# CH32F207VCT6-R0.net
KiCad netlist of a schematic drawn in Altium Designer
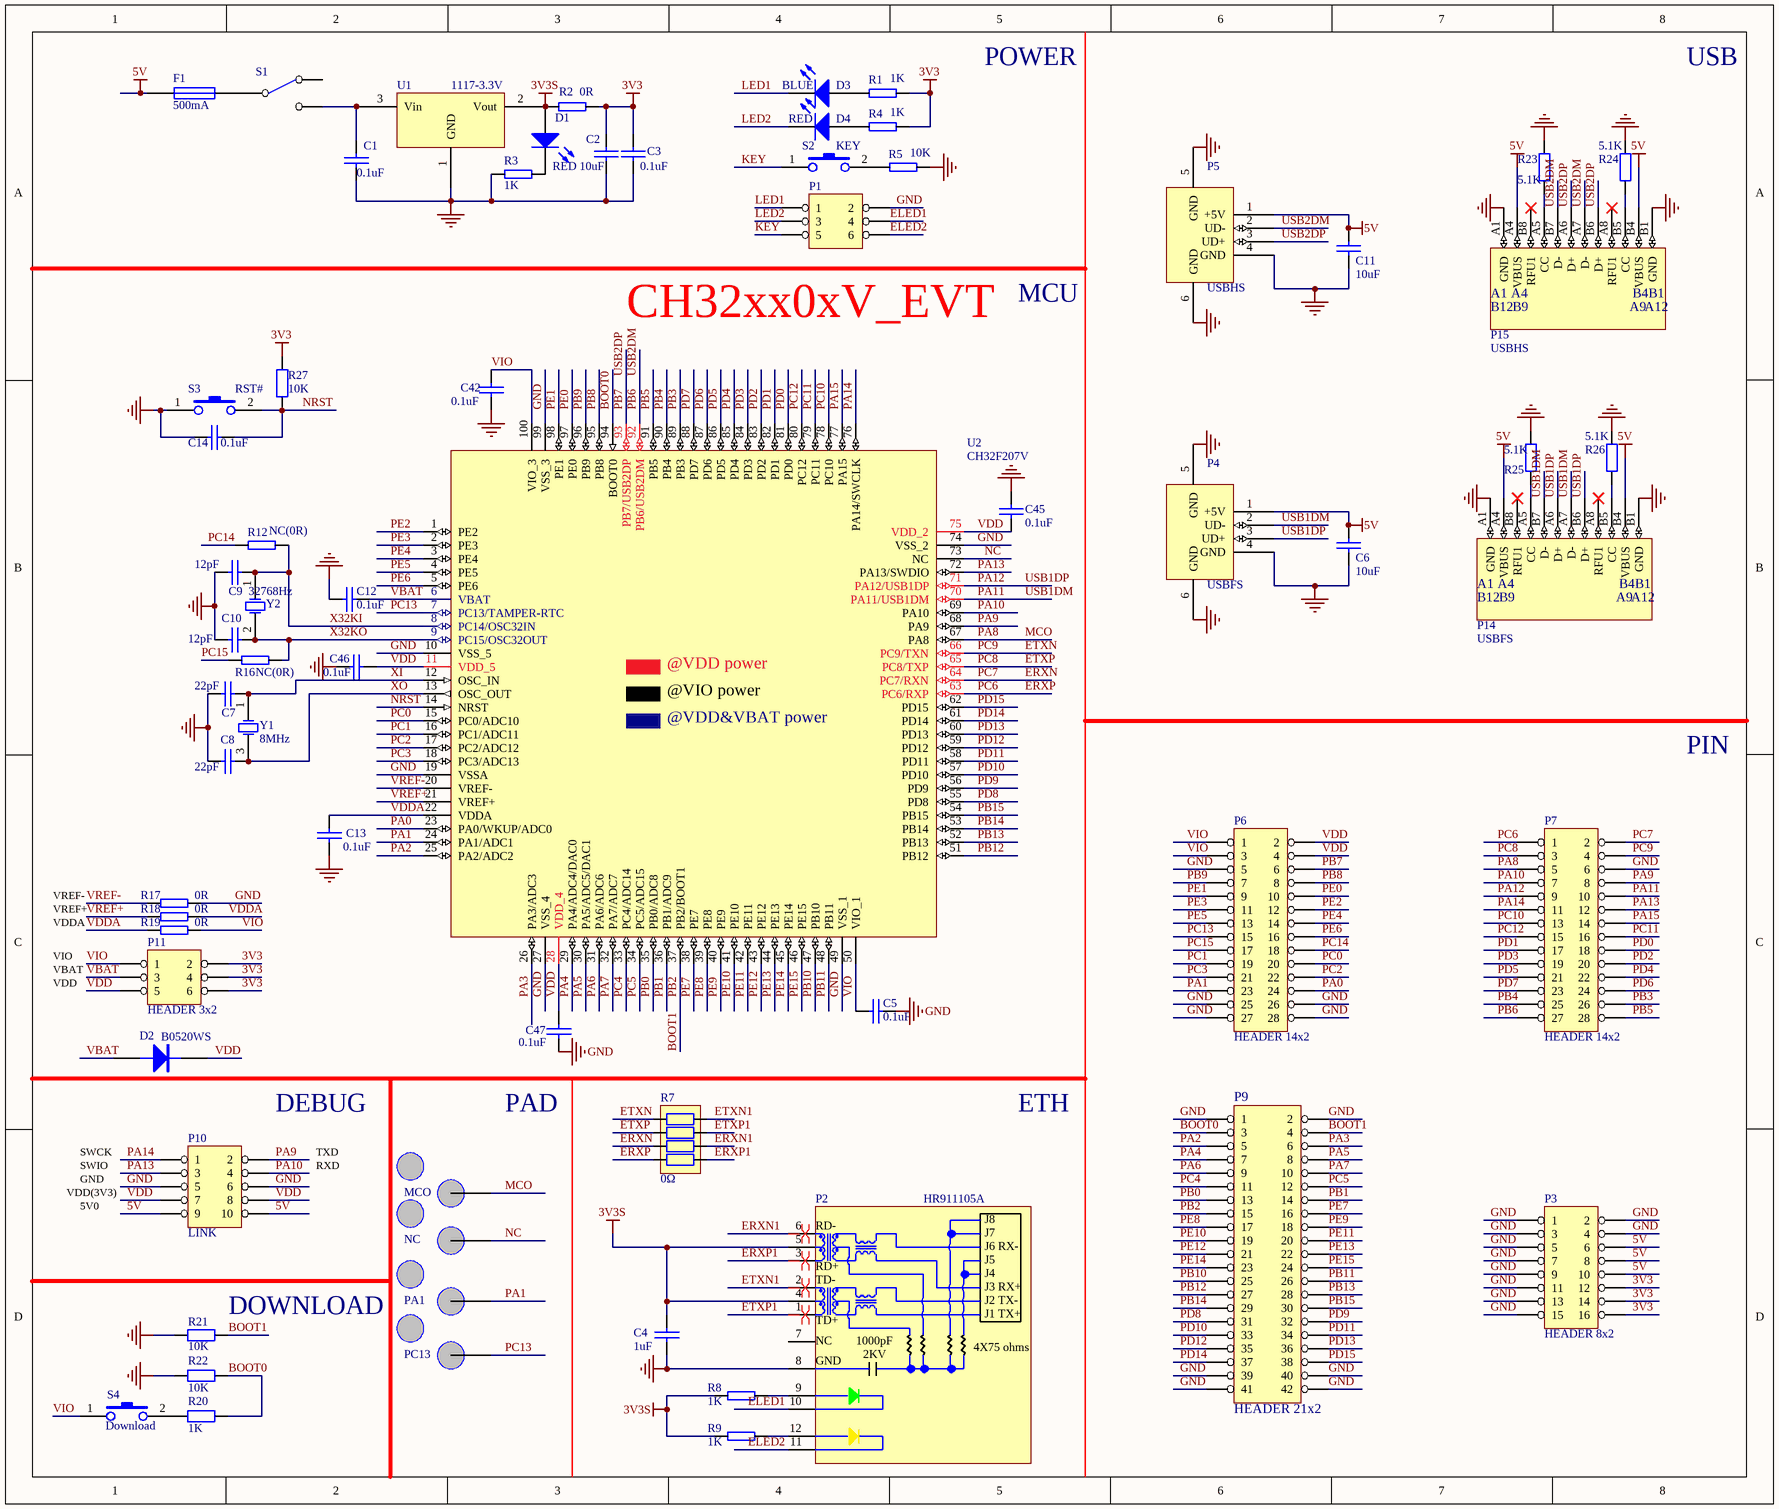
[diagram p0: CH32F207VCT6-R0.SchDoc]

(export (version "E")
  (design (tool "Eeschema 10.0.6"))
  (components
    (comp (ref "C1")
      (value "0.1uF")
      (footprint "0603_C")
      (description "Capacitor")
      (libsource (lib "") (part "CAP_1"))
    )
    (comp (ref "C2")
      (value "10uF")
      (footprint "3216_C")
      (description "Capacitor")
      (libsource (lib "") (part "CAP_1"))
    )
    (comp (ref "C3")
      (value "0.1uF")
      (footprint "0603_C")
      (description "Capacitor")
      (libsource (lib "") (part "CAP_1"))
    )
    (comp (ref "C4")
      (value "1uF")
      (footprint "0603_C")
      (description "Capacitor")
      (libsource (lib "") (part "CAP_1"))
    )
    (comp (ref "C5")
      (value "0.1uF")
      (footprint "0603_C")
      (description "Capacitor")
      (libsource (lib "") (part "CAP_1"))
    )
    (comp (ref "C6")
      (value "10uF")
      (footprint "3216_C")
      (description "Capacitor")
      (libsource (lib "*") (part "CAP"))
    )
    (comp (ref "C7")
      (value "22pF")
      (footprint "0603_C")
      (description "Capacitor")
      (libsource (lib "") (part "CAP_1"))
    )
    (comp (ref "C8")
      (value "22pF")
      (footprint "0603_C")
      (description "Capacitor")
      (libsource (lib "") (part "CAP_1"))
    )
    (comp (ref "C9")
      (value "12pF")
      (footprint "0603_C")
      (description "Capacitor")
      (libsource (lib "") (part "CAP_1"))
    )
    (comp (ref "C10")
      (value "12pF")
      (footprint "0603_C")
      (description "Capacitor")
      (libsource (lib "") (part "CAP_1"))
    )
    (comp (ref "C11")
      (value "10uF")
      (footprint "3216_C")
      (description "Capacitor")
      (libsource (lib "*") (part "CAP"))
    )
    (comp (ref "C12")
      (value "0.1uF")
      (footprint "0603_C")
      (description "Capacitor")
      (libsource (lib "") (part "CAP_1"))
    )
    (comp (ref "C13")
      (value "0.1uF")
      (footprint "0603_C")
      (description "Capacitor")
      (libsource (lib "") (part "CAP_1"))
    )
    (comp (ref "C14")
      (value "0.1uF")
      (footprint "0603_C")
      (description "Capacitor")
      (libsource (lib "*") (part "CAP"))
    )
    (comp (ref "C42")
      (value "0.1uF")
      (footprint "0603_C")
      (description "Capacitor")
      (libsource (lib "") (part "CAP_1"))
    )
    (comp (ref "C45")
      (value "0.1uF")
      (footprint "0603_C")
      (description "Capacitor")
      (libsource (lib "") (part "CAP_1"))
    )
    (comp (ref "C46")
      (value "0.1uF")
      (footprint "0603_C")
      (description "Capacitor")
      (libsource (lib "") (part "CAP_1"))
    )
    (comp (ref "C47")
      (value "0.1uF")
      (footprint "0603_C")
      (description "Capacitor")
      (libsource (lib "") (part "CAP_1"))
    )
    (comp (ref "D1")
      (value "RED")
      (footprint "0603+")
      (description "Typical INFRARED GaAs LED")
      (fields (field (name "PUBLISHER") "Altium Limited"))
      (libsource (lib "*") (part "LED0"))
    )
    (comp (ref "D2")
      (value "B0520WS")
      (footprint "SOD-323")
      (description "Diode")
      (libsource (lib "*") (part "DIODE"))
    )
    (comp (ref "D3")
      (value "BLUE")
      (footprint "0603+")
      (description "Typical INFRARED GaAs LED")
      (fields (field (name "PUBLISHER") "Altium Limited"))
      (libsource (lib "*") (part "LED0"))
    )
    (comp (ref "D4")
      (value "RED")
      (footprint "0603+")
      (description "Typical INFRARED GaAs LED")
      (fields (field (name "PUBLISHER") "Altium Limited"))
      (libsource (lib "*") (part "LED0"))
    )
    (comp (ref "F1")
      (value "500mA")
      (footprint "0805")
      (description "Fuse")
      (libsource (lib "wch_sch_others") (part "FUSE1"))
    )
    (comp (ref "MCO")
      (value "Testpoint")
      (footprint "TESTPOINT1")
      (description "测试点")
      (libsource (lib "wch_sch_others") (part "Testpoint"))
    )
    (comp (ref "NC")
      (value "Testpoint")
      (footprint "TESTPOINT1")
      (description "测试点")
      (libsource (lib "wch_sch_others") (part "Testpoint"))
    )
    (comp (ref "P1")
      (value "IO")
      (footprint "MYPCB:IDC6-2.54mm")
      (description "Header, 3-Pin, Dual row")
      (libsource (lib "wch_sch_others") (part "HEADER 3x2"))
    )
    (comp (ref "P2") (value "HR911105A") (footprint "HR911105A") (libsource (lib "*") (part "HR911105A")))
    (comp (ref "P3")
      (value "HEADER 8x2")
      (footprint "MYPCB:IDC16-2.54mm")
      (description "Header, 8-Pin, Dual row")
      (libsource (lib "wch_sch_others") (part "HEADER 8x2"))
    )
    (comp (ref "P4")
      (value "USBFS")
      (footprint "USBAF")
      (description "USB Port")
      (libsource (lib "*") (part "USB"))
    )
    (comp (ref "P5")
      (value "USBHS")
      (footprint "USBAF")
      (description "USB Port")
      (libsource (lib "*") (part "USB"))
    )
    (comp (ref "P6")
      (value "HEADER 14x2")
      (footprint "MYPCB:IDC28-2.54MM")
      (description "Header, 14-Pin, Dual row")
      (libsource (lib "wch_sch_others") (part "HEADER 14x2"))
    )
    (comp (ref "P7")
      (value "HEADER 14x2")
      (footprint "MYPCB:IDC28-2.54MM")
      (description "Header, 14-Pin, Dual row")
      (libsource (lib "wch_sch_others") (part "HEADER 14x2"))
    )
    (comp (ref "P9")
      (value "HEADER 21x2")
      (footprint "MYPCB:IDC42-2.54MM")
      (description "Header, 21-Pin, Dual row")
      (libsource (lib "wch_sch_others") (part "HEADER 21x2"))
    )
    (comp (ref "P10")
      (value "LINK")
      (footprint "MYPCB:IDC10-2.54mm")
      (description "Header, 5-Pin, Dual row")
      (libsource (lib "wch_sch_others") (part "HEADER 5x2"))
    )
    (comp (ref "P11")
      (value "HEADER 3x2")
      (footprint "MYPCB:IDC6-2.54mm")
      (description "Header, 3-Pin, Dual row")
      (libsource (lib "wch_sch_others") (part "HEADER 3x2"))
    )
    (comp (ref "P14")
      (value "USBFS")
      (footprint "TYPE-C-Receptacle-2.0")
      (libsource (lib "*") (part "TYPE-C1"))
    )
    (comp (ref "P15")
      (value "USBHS")
      (footprint "TYPE-C-Receptacle-2.0")
      (libsource (lib "*") (part "TYPE-C1"))
    )
    (comp (ref "PA1")
      (value "Testpoint")
      (footprint "TESTPOINT1")
      (description "测试点")
      (libsource (lib "wch_sch_others") (part "Testpoint"))
    )
    (comp (ref "PC13")
      (value "Testpoint")
      (footprint "TESTPOINT1")
      (description "测试点")
      (libsource (lib "wch_sch_others") (part "Testpoint"))
    )
    (comp (ref "R1") (value "1K") (footprint "0603") (libsource (lib "wch_sch_others") (part "RES")))
    (comp (ref "R2") (value "0R") (footprint "0603") (libsource (lib "wch_sch_others") (part "RES")))
    (comp (ref "R3") (value "1K") (footprint "0603") (libsource (lib "wch_sch_others") (part "RES")))
    (comp (ref "R4") (value "1K") (footprint "0603") (libsource (lib "wch_sch_others") (part "RES")))
    (comp (ref "R5") (value "10K") (footprint "0603") (libsource (lib "wch_sch_others") (part "RES")))
    (comp (ref "R7")
      (value "0Ω")
      (footprint "RCA-8P4R-0603")
      (description "贴片网络排阻")
      (fields (field (name "版权归属") "源创客"))
      (libsource (lib "wch_sch_others") (part "R-8P4R"))
    )
    (comp (ref "R8") (value "1K") (footprint "0603") (libsource (lib "wch_sch_others") (part "RES")))
    (comp (ref "R9") (value "1K") (footprint "0603") (libsource (lib "wch_sch_others") (part "RES")))
    (comp (ref "R12") (value "NC(0R)") (footprint "0603") (libsource (lib "wch_sch_others") (part "RES")))
    (comp (ref "R16") (value "NC(0R)") (footprint "0603") (libsource (lib "wch_sch_others") (part "RES")))
    (comp (ref "R17") (value "0R") (footprint "0603") (libsource (lib "*") (part "R")))
    (comp (ref "R18") (value "0R") (footprint "0603") (libsource (lib "*") (part "R")))
    (comp (ref "R19") (value "0R") (footprint "0603") (libsource (lib "*") (part "R")))
    (comp (ref "R20")
      (value "1K")
      (footprint "0603")
      (description "Resistor")
      (fields (field (name "PUBLISHER") "Altium Limited"))
      (libsource (lib "Miscellaneous Devices") (part "Res2"))
    )
    (comp (ref "R21")
      (value "10K")
      (footprint "0603")
      (description "Resistor")
      (fields (field (name "PUBLISHER") "Altium Limited"))
      (libsource (lib "Miscellaneous Devices") (part "Res2"))
    )
    (comp (ref "R22")
      (value "10K")
      (footprint "0603")
      (description "Resistor")
      (fields (field (name "PUBLISHER") "Altium Limited"))
      (libsource (lib "Miscellaneous Devices") (part "Res2"))
    )
    (comp (ref "R23")
      (value "5.1K")
      (footprint "0603")
      (description "Resistor")
      (libsource (lib "") (part "Res2_1"))
    )
    (comp (ref "R24")
      (value "5.1K")
      (footprint "0603")
      (description "Resistor")
      (libsource (lib "") (part "Res2_1"))
    )
    (comp (ref "R25")
      (value "5.1K")
      (footprint "0603")
      (description "Resistor")
      (libsource (lib "") (part "Res2_1"))
    )
    (comp (ref "R26")
      (value "5.1K")
      (footprint "0603")
      (description "Resistor")
      (libsource (lib "") (part "Res2_1"))
    )
    (comp (ref "R27")
      (value "10K")
      (footprint "0603")
      (description "Resistor")
      (fields (field (name "PUBLISHER") "Altium Limited"))
      (libsource (lib "") (part "Res2_1"))
    )
    (comp (ref "S1") (value "SW SPDT") (footprint "KEY2") (libsource (lib "*") (part "SW SPDT")))
    (comp (ref "S2")
      (value "KEY")
      (footprint "SMD_6.1x3.65x2.5mm-KEY")
      (libsource (lib "wch_sch_others") (part "KEY1"))
    )
    (comp (ref "S3")
      (value "RST#")
      (footprint "SMD_6.1x3.65x2.5mm-KEY")
      (libsource (lib "wch_sch_others") (part "KEY1"))
    )
    (comp (ref "S4")
      (value "Download")
      (footprint "SMD_6.1x3.65x2.5mm-KEY")
      (libsource (lib "wch_sch_others") (part "KEY1"))
    )
    (comp (ref "U1")
      (value "1117-3.3V")
      (footprint "SOT-223")
      (libsource (lib "wch_sch_others") (part "1117-3.3V"))
    )
    (comp (ref "U2")
      (value "CH32F207V")
      (footprint "LQFP100")
      (description "ARM M3 HD-MCU, 144MHz, USB_480M, USB OTG, 1000M Ethernet MAC, 2*CAN")
      (libsource (lib "CHXXX") (part "CH32F207V"))
    )
    (comp (ref "Y1")
      (value "8MHz")
      (footprint "XT3225")
      (description "Crystal Oscillator")
      (fields (field (name "PUBLISHER") "Altium Limited"))
      (libsource (lib "*") (part "XTAL"))
    )
    (comp (ref "Y2")
      (value "32768Hz")
      (footprint "FC-135")
      (description "Crystal Oscillator")
      (fields (field (name "PUBLISHER") "Altium Limited"))
      (libsource (lib "") (part "XTAL_1"))
    )
  )
  (nets
    (net (code "2") (name "/BOOT0") (class "Default")
      (node (ref "P9") (pin "3") (pinfunction "3_3") (pintype "passive"))
      (node (ref "R20") (pin "1") (pinfunction "1_1") (pintype "passive"))
      (node (ref "R22") (pin "1") (pinfunction "1_1") (pintype "passive"))
      (node (ref "U2") (pin "94") (pinfunction "BOOT0_94") (pintype "input"))
    )
    (net (code "3") (name "/BOOT1") (class "Default")
      (node (ref "P9") (pin "15") (pinfunction "15_15") (pintype "passive"))
      (node (ref "P9") (pin "4") (pinfunction "4_4") (pintype "passive"))
      (node (ref "R21") (pin "1") (pinfunction "1_1") (pintype "passive"))
      (node (ref "U2") (pin "37") (pinfunction "PB2/BOOT1_37") (pintype "bidirectional"))
    )
    (net (code "4") (name "/ELED1") (class "Default")
      (node (ref "P1") (pin "4") (pinfunction "4_4") (pintype "passive"))
      (node (ref "P2") (pin "10") (pintype "passive"))
    )
    (net (code "5") (name "/ELED2") (class "Default")
      (node (ref "P1") (pin "6") (pinfunction "6_6") (pintype "passive"))
      (node (ref "P2") (pin "11") (pintype "passive"))
    )
    (net (code "6") (name "/ERXN") (class "Default")
      (node (ref "P7") (pin "2") (pinfunction "2_2") (pintype "passive"))
      (node (ref "R7") (pin "3") (pinfunction "3_3") (pintype "passive"))
      (node (ref "U2") (pin "64") (pinfunction "PC7/RXN_64") (pintype "bidirectional"))
    )
    (net (code "7") (name "/ERXN1") (class "Default")
      (node (ref "P2") (pin "6") (pintype "passive"))
      (node (ref "R7") (pin "6") (pinfunction "6_6") (pintype "passive"))
    )
    (net (code "8") (name "/ERXP") (class "Default")
      (node (ref "P7") (pin "1") (pinfunction "1_1") (pintype "passive"))
      (node (ref "R7") (pin "4") (pinfunction "4_4") (pintype "passive"))
      (node (ref "U2") (pin "63") (pinfunction "PC6/RXP_63") (pintype "bidirectional"))
    )
    (net (code "9") (name "/ERXP1") (class "Default")
      (node (ref "P2") (pin "3") (pintype "passive"))
      (node (ref "R7") (pin "5") (pinfunction "5_5") (pintype "passive"))
    )
    (net (code "10") (name "/ETXN") (class "Default")
      (node (ref "P7") (pin "4") (pinfunction "4_4") (pintype "passive"))
      (node (ref "R7") (pin "1") (pinfunction "1_1") (pintype "passive"))
      (node (ref "U2") (pin "66") (pinfunction "PC9/TXN_66") (pintype "bidirectional"))
    )
    (net (code "11") (name "/ETXN1") (class "Default")
      (node (ref "P2") (pin "2") (pintype "passive"))
      (node (ref "R7") (pin "8") (pinfunction "8_8") (pintype "passive"))
    )
    (net (code "12") (name "/ETXP") (class "Default")
      (node (ref "P7") (pin "3") (pinfunction "3_3") (pintype "passive"))
      (node (ref "R7") (pin "2") (pinfunction "2_2") (pintype "passive"))
      (node (ref "U2") (pin "65") (pinfunction "PC8/TXP_65") (pintype "bidirectional"))
    )
    (net (code "13") (name "/ETXP1") (class "Default")
      (node (ref "P2") (pin "1") (pintype "passive"))
      (node (ref "R7") (pin "7") (pinfunction "7_7") (pintype "passive"))
    )
    (net (code "14") (name "/KEY") (class "Default")
      (node (ref "P1") (pin "5") (pinfunction "5_5") (pintype "passive"))
      (node (ref "S2") (pin "1") (pinfunction "1_1") (pintype "passive"))
    )
    (net (code "15") (name "/LED1") (class "Default")
      (node (ref "D3") (pin "2") (pinfunction "K_2") (pintype "passive"))
      (node (ref "P1") (pin "1") (pinfunction "1_1") (pintype "passive"))
    )
    (net (code "16") (name "/LED2") (class "Default")
      (node (ref "D4") (pin "2") (pinfunction "K_2") (pintype "passive"))
      (node (ref "P1") (pin "3") (pinfunction "3_3") (pintype "passive"))
    )
    (net (code "17") (name "/MCO") (class "Default")
      (node (ref "MCO") (pin "1") (pinfunction "point_1") (pintype "passive"))
      (node (ref "P7") (pin "5") (pinfunction "5_5") (pintype "passive"))
      (node (ref "U2") (pin "67") (pinfunction "PA8_67") (pintype "bidirectional"))
    )
    (net (code "18") (name "/NC") (class "Default")
      (node (ref "NC") (pin "1") (pinfunction "point_1") (pintype "passive"))
      (node (ref "U2") (pin "73") (pinfunction "NC_73") (pintype "tri_state"))
    )
    (net (code "19") (name "/NRST") (class "Default")
      (node (ref "C14") (pin "2") (pinfunction "2_2") (pintype "passive"))
      (node (ref "R27") (pin "1") (pinfunction "1_1") (pintype "passive"))
      (node (ref "S3") (pin "2") (pinfunction "2_2") (pintype "passive"))
      (node (ref "U2") (pin "14") (pinfunction "NRST_14") (pintype "input"))
    )
    (net (code "20") (name "/PA0") (class "Default")
      (node (ref "P6") (pin "24") (pinfunction "24_24") (pintype "passive"))
      (node (ref "U2") (pin "23") (pinfunction "PA0/WKUP/ADC0_23") (pintype "bidirectional"))
    )
    (net (code "21") (name "/PA1") (class "Default")
      (node (ref "P6") (pin "23") (pinfunction "23_23") (pintype "passive"))
      (node (ref "PA1") (pin "1") (pinfunction "point_1") (pintype "passive"))
      (node (ref "U2") (pin "24") (pinfunction "PA1/ADC1_24") (pintype "bidirectional"))
    )
    (net (code "22") (name "/PA2") (class "Default")
      (node (ref "P9") (pin "5") (pinfunction "5_5") (pintype "passive"))
      (node (ref "U2") (pin "25") (pinfunction "PA2/ADC2_25") (pintype "bidirectional"))
    )
    (net (code "23") (name "/PA3") (class "Default")
      (node (ref "P9") (pin "6") (pinfunction "6_6") (pintype "passive"))
      (node (ref "U2") (pin "26") (pinfunction "PA3/ADC3_26") (pintype "bidirectional"))
    )
    (net (code "24") (name "/PA4") (class "Default")
      (node (ref "P9") (pin "7") (pinfunction "7_7") (pintype "passive"))
      (node (ref "U2") (pin "29") (pinfunction "PA4/ADC4/DAC0_29") (pintype "bidirectional"))
    )
    (net (code "25") (name "/PA5") (class "Default")
      (node (ref "P9") (pin "8") (pinfunction "8_8") (pintype "passive"))
      (node (ref "U2") (pin "30") (pinfunction "PA5/ADC5/DAC1_30") (pintype "bidirectional"))
    )
    (net (code "26") (name "/PA6") (class "Default")
      (node (ref "P9") (pin "9") (pinfunction "9_9") (pintype "passive"))
      (node (ref "U2") (pin "31") (pinfunction "PA6/ADC6_31") (pintype "bidirectional"))
    )
    (net (code "27") (name "/PA7") (class "Default")
      (node (ref "P9") (pin "10") (pinfunction "10_10") (pintype "passive"))
      (node (ref "U2") (pin "32") (pinfunction "PA7/ADC7_32") (pintype "bidirectional"))
    )
    (net (code "28") (name "/PA9") (class "Default")
      (node (ref "P10") (pin "2") (pinfunction "2_2") (pintype "passive"))
      (node (ref "P7") (pin "8") (pinfunction "8_8") (pintype "passive"))
      (node (ref "U2") (pin "68") (pinfunction "PA9_68") (pintype "bidirectional"))
    )
    (net (code "29") (name "/PA10") (class "Default")
      (node (ref "P10") (pin "4") (pinfunction "4_4") (pintype "passive"))
      (node (ref "P7") (pin "7") (pinfunction "7_7") (pintype "passive"))
      (node (ref "U2") (pin "69") (pinfunction "PA10_69") (pintype "bidirectional"))
    )
    (net (code "30") (name "/PA11") (class "Default")
      (node (ref "P14") (pin "A7") (pinfunction "D-_A7") (pintype "bidirectional"))
      (node (ref "P14") (pin "B7") (pinfunction "D-_B7") (pintype "bidirectional"))
      (node (ref "P4") (pin "2") (pinfunction "UD-_2") (pintype "bidirectional"))
      (node (ref "P7") (pin "10") (pinfunction "10_10") (pintype "passive"))
      (node (ref "U2") (pin "70") (pinfunction "PA11/USB1DM_70") (pintype "bidirectional"))
    )
    (net (code "31") (name "/PA12") (class "Default")
      (node (ref "P14") (pin "A6") (pinfunction "D+_A6") (pintype "bidirectional"))
      (node (ref "P14") (pin "B6") (pinfunction "D+_B6") (pintype "bidirectional"))
      (node (ref "P4") (pin "3") (pinfunction "UD+_3") (pintype "bidirectional"))
      (node (ref "P7") (pin "9") (pinfunction "9_9") (pintype "passive"))
      (node (ref "U2") (pin "71") (pinfunction "PA12/USB1DP_71") (pintype "bidirectional"))
    )
    (net (code "32") (name "/PA13") (class "Default")
      (node (ref "P10") (pin "3") (pinfunction "3_3") (pintype "passive"))
      (node (ref "P7") (pin "12") (pinfunction "12_12") (pintype "passive"))
      (node (ref "U2") (pin "72") (pinfunction "PA13/SWDIO_72") (pintype "bidirectional"))
    )
    (net (code "33") (name "/PA14") (class "Default")
      (node (ref "P10") (pin "1") (pinfunction "1_1") (pintype "passive"))
      (node (ref "P7") (pin "11") (pinfunction "11_11") (pintype "passive"))
      (node (ref "U2") (pin "76") (pinfunction "PA14/SWCLK_76") (pintype "bidirectional"))
    )
    (net (code "34") (name "/PA15") (class "Default")
      (node (ref "P7") (pin "14") (pinfunction "14_14") (pintype "passive"))
      (node (ref "U2") (pin "77") (pinfunction "PA15_77") (pintype "bidirectional"))
    )
    (net (code "35") (name "/PB0") (class "Default")
      (node (ref "P9") (pin "13") (pinfunction "13_13") (pintype "passive"))
      (node (ref "U2") (pin "35") (pinfunction "PB0/ADC8_35") (pintype "bidirectional"))
    )
    (net (code "36") (name "/PB1") (class "Default")
      (node (ref "P9") (pin "14") (pinfunction "14_14") (pintype "passive"))
      (node (ref "U2") (pin "36") (pinfunction "PB1/ADC9_36") (pintype "bidirectional"))
    )
    (net (code "37") (name "/PB3") (class "Default")
      (node (ref "P7") (pin "26") (pinfunction "26_26") (pintype "passive"))
      (node (ref "U2") (pin "89") (pinfunction "PB3_89") (pintype "bidirectional"))
    )
    (net (code "38") (name "/PB4") (class "Default")
      (node (ref "P7") (pin "25") (pinfunction "25_25") (pintype "passive"))
      (node (ref "U2") (pin "90") (pinfunction "PB4_90") (pintype "bidirectional"))
    )
    (net (code "39") (name "/PB5") (class "Default")
      (node (ref "P7") (pin "28") (pinfunction "28_28") (pintype "passive"))
      (node (ref "U2") (pin "91") (pinfunction "PB5_91") (pintype "bidirectional"))
    )
    (net (code "40") (name "/PB6") (class "Default")
      (node (ref "P15") (pin "A7") (pinfunction "D-_A7") (pintype "bidirectional"))
      (node (ref "P15") (pin "B7") (pinfunction "D-_B7") (pintype "bidirectional"))
      (node (ref "P5") (pin "2") (pinfunction "UD-_2") (pintype "bidirectional"))
      (node (ref "P7") (pin "27") (pinfunction "27_27") (pintype "passive"))
      (node (ref "U2") (pin "92") (pinfunction "PB6/USB2DM_92") (pintype "bidirectional"))
    )
    (net (code "41") (name "/PB7") (class "Default")
      (node (ref "P15") (pin "A6") (pinfunction "D+_A6") (pintype "bidirectional"))
      (node (ref "P15") (pin "B6") (pinfunction "D+_B6") (pintype "bidirectional"))
      (node (ref "P5") (pin "3") (pinfunction "UD+_3") (pintype "bidirectional"))
      (node (ref "P6") (pin "6") (pinfunction "6_6") (pintype "passive"))
      (node (ref "U2") (pin "93") (pinfunction "PB7/USB2DP_93") (pintype "bidirectional"))
    )
    (net (code "42") (name "/PB8") (class "Default")
      (node (ref "P6") (pin "8") (pinfunction "8_8") (pintype "passive"))
      (node (ref "U2") (pin "95") (pinfunction "PB8_95") (pintype "bidirectional"))
    )
    (net (code "43") (name "/PB9") (class "Default")
      (node (ref "P6") (pin "7") (pinfunction "7_7") (pintype "passive"))
      (node (ref "U2") (pin "96") (pinfunction "PB9_96") (pintype "bidirectional"))
    )
    (net (code "44") (name "/PB10") (class "Default")
      (node (ref "P9") (pin "25") (pinfunction "25_25") (pintype "passive"))
      (node (ref "U2") (pin "47") (pinfunction "PB10_47") (pintype "bidirectional"))
    )
    (net (code "45") (name "/PB11") (class "Default")
      (node (ref "P9") (pin "26") (pinfunction "26_26") (pintype "passive"))
      (node (ref "U2") (pin "48") (pinfunction "PB11_48") (pintype "bidirectional"))
    )
    (net (code "46") (name "/PB12") (class "Default")
      (node (ref "P9") (pin "27") (pinfunction "27_27") (pintype "passive"))
      (node (ref "U2") (pin "51") (pinfunction "PB12_51") (pintype "bidirectional"))
    )
    (net (code "47") (name "/PB13") (class "Default")
      (node (ref "P9") (pin "28") (pinfunction "28_28") (pintype "passive"))
      (node (ref "U2") (pin "52") (pinfunction "PB13_52") (pintype "bidirectional"))
    )
    (net (code "48") (name "/PB14") (class "Default")
      (node (ref "P9") (pin "29") (pinfunction "29_29") (pintype "passive"))
      (node (ref "U2") (pin "53") (pinfunction "PB14_53") (pintype "bidirectional"))
    )
    (net (code "49") (name "/PB15") (class "Default")
      (node (ref "P9") (pin "30") (pinfunction "30_30") (pintype "passive"))
      (node (ref "U2") (pin "54") (pinfunction "PB15_54") (pintype "bidirectional"))
    )
    (net (code "50") (name "/PC0") (class "Default")
      (node (ref "P6") (pin "20") (pinfunction "20_20") (pintype "passive"))
      (node (ref "U2") (pin "15") (pinfunction "PC0/ADC10_15") (pintype "bidirectional"))
    )
    (net (code "51") (name "/PC1") (class "Default")
      (node (ref "P6") (pin "19") (pinfunction "19_19") (pintype "passive"))
      (node (ref "U2") (pin "16") (pinfunction "PC1/ADC11_16") (pintype "bidirectional"))
    )
    (net (code "52") (name "/PC2") (class "Default")
      (node (ref "P6") (pin "22") (pinfunction "22_22") (pintype "passive"))
      (node (ref "U2") (pin "17") (pinfunction "PC2/ADC12_17") (pintype "bidirectional"))
    )
    (net (code "53") (name "/PC3") (class "Default")
      (node (ref "P6") (pin "21") (pinfunction "21_21") (pintype "passive"))
      (node (ref "U2") (pin "18") (pinfunction "PC3/ADC13_18") (pintype "bidirectional"))
    )
    (net (code "54") (name "/PC4") (class "Default")
      (node (ref "P9") (pin "11") (pinfunction "11_11") (pintype "passive"))
      (node (ref "U2") (pin "33") (pinfunction "PC4/ADC14_33") (pintype "bidirectional"))
    )
    (net (code "55") (name "/PC5") (class "Default")
      (node (ref "P9") (pin "12") (pinfunction "12_12") (pintype "passive"))
      (node (ref "U2") (pin "34") (pinfunction "PC5/ADC15_34") (pintype "bidirectional"))
    )
    (net (code "56") (name "/PC10") (class "Default")
      (node (ref "P7") (pin "13") (pinfunction "13_13") (pintype "passive"))
      (node (ref "U2") (pin "78") (pinfunction "PC10_78") (pintype "bidirectional"))
    )
    (net (code "57") (name "/PC11") (class "Default")
      (node (ref "P7") (pin "16") (pinfunction "16_16") (pintype "passive"))
      (node (ref "U2") (pin "79") (pinfunction "PC11_79") (pintype "bidirectional"))
    )
    (net (code "58") (name "/PC12") (class "Default")
      (node (ref "P7") (pin "15") (pinfunction "15_15") (pintype "passive"))
      (node (ref "U2") (pin "80") (pinfunction "PC12_80") (pintype "bidirectional"))
    )
    (net (code "59") (name "/PC13") (class "Default")
      (node (ref "P6") (pin "15") (pinfunction "15_15") (pintype "passive"))
      (node (ref "PC13") (pin "1") (pinfunction "point_1") (pintype "passive"))
      (node (ref "U2") (pin "7") (pinfunction "PC13/TAMPER-RTC_7") (pintype "bidirectional"))
    )
    (net (code "60") (name "/PC14") (class "Default")
      (node (ref "P6") (pin "18") (pinfunction "18_18") (pintype "passive"))
      (node (ref "R12") (pin "1") (pintype "passive"))
    )
    (net (code "61") (name "/PC15") (class "Default")
      (node (ref "P6") (pin "17") (pinfunction "17_17") (pintype "passive"))
      (node (ref "R16") (pin "1") (pintype "passive"))
    )
    (net (code "62") (name "/PD0") (class "Default")
      (node (ref "P7") (pin "18") (pinfunction "18_18") (pintype "passive"))
      (node (ref "U2") (pin "81") (pinfunction "PD0_81") (pintype "bidirectional"))
    )
    (net (code "63") (name "/PD1") (class "Default")
      (node (ref "P7") (pin "17") (pinfunction "17_17") (pintype "passive"))
      (node (ref "U2") (pin "82") (pinfunction "PD1_82") (pintype "bidirectional"))
    )
    (net (code "64") (name "/PD2") (class "Default")
      (node (ref "P7") (pin "20") (pinfunction "20_20") (pintype "passive"))
      (node (ref "U2") (pin "83") (pinfunction "PD2_83") (pintype "bidirectional"))
    )
    (net (code "65") (name "/PD3") (class "Default")
      (node (ref "P7") (pin "19") (pinfunction "19_19") (pintype "passive"))
      (node (ref "U2") (pin "84") (pinfunction "PD3_84") (pintype "bidirectional"))
    )
    (net (code "66") (name "/PD4") (class "Default")
      (node (ref "P7") (pin "22") (pinfunction "22_22") (pintype "passive"))
      (node (ref "U2") (pin "85") (pinfunction "PD4_85") (pintype "bidirectional"))
    )
    (net (code "67") (name "/PD5") (class "Default")
      (node (ref "P7") (pin "21") (pinfunction "21_21") (pintype "passive"))
      (node (ref "U2") (pin "86") (pinfunction "PD5_86") (pintype "bidirectional"))
    )
    (net (code "68") (name "/PD6") (class "Default")
      (node (ref "P7") (pin "24") (pinfunction "24_24") (pintype "passive"))
      (node (ref "U2") (pin "87") (pinfunction "PD6_87") (pintype "bidirectional"))
    )
    (net (code "69") (name "/PD7") (class "Default")
      (node (ref "P7") (pin "23") (pinfunction "23_23") (pintype "passive"))
      (node (ref "U2") (pin "88") (pinfunction "PD7_88") (pintype "bidirectional"))
    )
    (net (code "70") (name "/PD8") (class "Default")
      (node (ref "P9") (pin "31") (pinfunction "31_31") (pintype "passive"))
      (node (ref "U2") (pin "55") (pinfunction "PD8_55") (pintype "bidirectional"))
    )
    (net (code "71") (name "/PD9") (class "Default")
      (node (ref "P9") (pin "32") (pinfunction "32_32") (pintype "passive"))
      (node (ref "U2") (pin "56") (pinfunction "PD9_56") (pintype "bidirectional"))
    )
    (net (code "72") (name "/PD10") (class "Default")
      (node (ref "P9") (pin "33") (pinfunction "33_33") (pintype "passive"))
      (node (ref "U2") (pin "57") (pinfunction "PD10_57") (pintype "bidirectional"))
    )
    (net (code "73") (name "/PD11") (class "Default")
      (node (ref "P9") (pin "34") (pinfunction "34_34") (pintype "passive"))
      (node (ref "U2") (pin "58") (pinfunction "PD11_58") (pintype "bidirectional"))
    )
    (net (code "74") (name "/PD12") (class "Default")
      (node (ref "P9") (pin "35") (pinfunction "35_35") (pintype "passive"))
      (node (ref "U2") (pin "59") (pinfunction "PD12_59") (pintype "bidirectional"))
    )
    (net (code "75") (name "/PD13") (class "Default")
      (node (ref "P9") (pin "36") (pinfunction "36_36") (pintype "passive"))
      (node (ref "U2") (pin "60") (pinfunction "PD13_60") (pintype "bidirectional"))
    )
    (net (code "76") (name "/PD14") (class "Default")
      (node (ref "P9") (pin "37") (pinfunction "37_37") (pintype "passive"))
      (node (ref "U2") (pin "61") (pinfunction "PD14_61") (pintype "bidirectional"))
    )
    (net (code "77") (name "/PD15") (class "Default")
      (node (ref "P9") (pin "38") (pinfunction "38_38") (pintype "passive"))
      (node (ref "U2") (pin "62") (pinfunction "PD15_62") (pintype "bidirectional"))
    )
    (net (code "78") (name "/PE0") (class "Default")
      (node (ref "P6") (pin "10") (pinfunction "10_10") (pintype "passive"))
      (node (ref "U2") (pin "97") (pinfunction "PE0_97") (pintype "bidirectional"))
    )
    (net (code "79") (name "/PE1") (class "Default")
      (node (ref "P6") (pin "9") (pinfunction "9_9") (pintype "passive"))
      (node (ref "U2") (pin "98") (pinfunction "PE1_98") (pintype "bidirectional"))
    )
    (net (code "80") (name "/PE2") (class "Default")
      (node (ref "P6") (pin "12") (pinfunction "12_12") (pintype "passive"))
      (node (ref "U2") (pin "1") (pinfunction "PE2_1") (pintype "bidirectional"))
    )
    (net (code "81") (name "/PE3") (class "Default")
      (node (ref "P6") (pin "11") (pinfunction "11_11") (pintype "passive"))
      (node (ref "U2") (pin "2") (pinfunction "PE3_2") (pintype "bidirectional"))
    )
    (net (code "82") (name "/PE4") (class "Default")
      (node (ref "P6") (pin "14") (pinfunction "14_14") (pintype "passive"))
      (node (ref "U2") (pin "3") (pinfunction "PE4_3") (pintype "bidirectional"))
    )
    (net (code "83") (name "/PE5") (class "Default")
      (node (ref "P6") (pin "13") (pinfunction "13_13") (pintype "passive"))
      (node (ref "U2") (pin "4") (pinfunction "PE5_4") (pintype "bidirectional"))
    )
    (net (code "84") (name "/PE6") (class "Default")
      (node (ref "P6") (pin "16") (pinfunction "16_16") (pintype "passive"))
      (node (ref "U2") (pin "5") (pinfunction "PE6_5") (pintype "bidirectional"))
    )
    (net (code "85") (name "/PE7") (class "Default")
      (node (ref "P9") (pin "16") (pinfunction "16_16") (pintype "passive"))
      (node (ref "U2") (pin "38") (pinfunction "PE7_38") (pintype "bidirectional"))
    )
    (net (code "86") (name "/PE8") (class "Default")
      (node (ref "P9") (pin "17") (pinfunction "17_17") (pintype "passive"))
      (node (ref "U2") (pin "39") (pinfunction "PE8_39") (pintype "bidirectional"))
    )
    (net (code "87") (name "/PE9") (class "Default")
      (node (ref "P9") (pin "18") (pinfunction "18_18") (pintype "passive"))
      (node (ref "U2") (pin "40") (pinfunction "PE9_40") (pintype "bidirectional"))
    )
    (net (code "88") (name "/PE10") (class "Default")
      (node (ref "P9") (pin "19") (pinfunction "19_19") (pintype "passive"))
      (node (ref "U2") (pin "41") (pinfunction "PE10_41") (pintype "bidirectional"))
    )
    (net (code "89") (name "/PE11") (class "Default")
      (node (ref "P9") (pin "20") (pinfunction "20_20") (pintype "passive"))
      (node (ref "U2") (pin "42") (pinfunction "PE11_42") (pintype "bidirectional"))
    )
    (net (code "90") (name "/PE12") (class "Default")
      (node (ref "P9") (pin "21") (pinfunction "21_21") (pintype "passive"))
      (node (ref "U2") (pin "43") (pinfunction "PE12_43") (pintype "bidirectional"))
    )
    (net (code "91") (name "/PE13") (class "Default")
      (node (ref "P9") (pin "22") (pinfunction "22_22") (pintype "passive"))
      (node (ref "U2") (pin "44") (pinfunction "PE13_44") (pintype "bidirectional"))
    )
    (net (code "92") (name "/PE14") (class "Default")
      (node (ref "P9") (pin "23") (pinfunction "23_23") (pintype "passive"))
      (node (ref "U2") (pin "45") (pinfunction "PE14_45") (pintype "bidirectional"))
    )
    (net (code "93") (name "/PE15") (class "Default")
      (node (ref "P9") (pin "24") (pinfunction "24_24") (pintype "passive"))
      (node (ref "U2") (pin "46") (pinfunction "PE15_46") (pintype "bidirectional"))
    )
    (net (code "94") (name "/VBAT") (class "Default")
      (node (ref "C12") (pin "2") (pinfunction "2_2") (pintype "passive"))
      (node (ref "D2") (pin "1") (pinfunction "A_1") (pintype "passive"))
      (node (ref "P11") (pin "3") (pinfunction "3_3") (pintype "passive"))
      (node (ref "U2") (pin "6") (pinfunction "VBAT_6") (pintype "power_in"))
    )
    (net (code "95") (name "/VDD") (class "Default")
      (node (ref "C45") (pin "1") (pinfunction "1_1") (pintype "passive"))
      (node (ref "C46") (pin "1") (pinfunction "1_1") (pintype "passive"))
      (node (ref "C47") (pin "2") (pinfunction "2_2") (pintype "passive"))
      (node (ref "D2") (pin "2") (pinfunction "K_2") (pintype "passive"))
      (node (ref "P10") (pin "7") (pinfunction "7_7") (pintype "passive"))
      (node (ref "P10") (pin "8") (pinfunction "8_8") (pintype "passive"))
      (node (ref "P11") (pin "5") (pinfunction "5_5") (pintype "passive"))
      (node (ref "P6") (pin "2") (pinfunction "2_2") (pintype "passive"))
      (node (ref "P6") (pin "4") (pinfunction "4_4") (pintype "passive"))
      (node (ref "U2") (pin "11") (pinfunction "VDD_5_11") (pintype "power_in"))
      (node (ref "U2") (pin "28") (pinfunction "VDD_4_28") (pintype "power_in"))
      (node (ref "U2") (pin "75") (pinfunction "VDD_2_75") (pintype "power_in"))
    )
    (net (code "96") (name "/VDDA") (class "Default")
      (node (ref "C13") (pin "1") (pinfunction "1_1") (pintype "passive"))
      (node (ref "R18") (pin "1") (pinfunction "1_1") (pintype "passive"))
      (node (ref "R19") (pin "2") (pinfunction "2_2") (pintype "passive"))
      (node (ref "U2") (pin "22") (pinfunction "VDDA_22") (pintype "power_in"))
    )
    (net (code "97") (name "/VIO") (class "Default")
      (node (ref "C42") (pin "2") (pinfunction "2_2") (pintype "passive"))
      (node (ref "C5") (pin "1") (pinfunction "1_1") (pintype "passive"))
      (node (ref "P11") (pin "1") (pinfunction "1_1") (pintype "passive"))
      (node (ref "P6") (pin "1") (pinfunction "1_1") (pintype "passive"))
      (node (ref "P6") (pin "3") (pinfunction "3_3") (pintype "passive"))
      (node (ref "R19") (pin "1") (pinfunction "1_1") (pintype "passive"))
      (node (ref "S4") (pin "1") (pinfunction "1_1") (pintype "passive"))
      (node (ref "U2") (pin "100") (pinfunction "VIO_3_100") (pintype "power_in"))
      (node (ref "U2") (pin "50") (pinfunction "VIO_1_50") (pintype "power_in"))
    )
    (net (code "98") (name "/VREF+") (class "Default")
      (node (ref "R18") (pin "2") (pinfunction "2_2") (pintype "passive"))
      (node (ref "U2") (pin "21") (pinfunction "VREF+_21") (pintype "power_in"))
    )
    (net (code "99") (name "/VREF-") (class "Default")
      (node (ref "R17") (pin "2") (pinfunction "2_2") (pintype "passive"))
      (node (ref "U2") (pin "20") (pinfunction "VREF-_20") (pintype "power_in"))
    )
    (net (code "100") (name "/X32KI") (class "Default")
      (node (ref "C9") (pin "2") (pinfunction "2_2") (pintype "passive"))
      (node (ref "R12") (pin "2") (pintype "passive"))
      (node (ref "U2") (pin "8") (pinfunction "PC14/OSC32IN_8") (pintype "bidirectional"))
      (node (ref "Y2") (pin "1") (pinfunction "OSC1_1") (pintype "passive"))
    )
    (net (code "101") (name "/X32KO") (class "Default")
      (node (ref "C10") (pin "2") (pinfunction "2_2") (pintype "passive"))
      (node (ref "R16") (pin "2") (pintype "passive"))
      (node (ref "U2") (pin "9") (pinfunction "PC15/OSC32OUT_9") (pintype "bidirectional"))
      (node (ref "Y2") (pin "2") (pinfunction "OSC2_2") (pintype "passive"))
    )
    (net (code "102") (name "/XI") (class "Default")
      (node (ref "C7") (pin "2") (pinfunction "2_2") (pintype "passive"))
      (node (ref "U2") (pin "12") (pinfunction "OSC_IN_12") (pintype "input"))
      (node (ref "Y1") (pin "1") (pinfunction "OSC1_1") (pintype "passive"))
    )
    (net (code "103") (name "/XO") (class "Default")
      (node (ref "C8") (pin "2") (pinfunction "2_2") (pintype "passive"))
      (node (ref "U2") (pin "13") (pinfunction "OSC_OUT_13") (pintype "output"))
      (node (ref "Y1") (pin "3") (pinfunction "OSC2_3") (pintype "passive"))
    )
    (net (code "104") (name "3V3") (class "Default")
      (node (ref "C2") (pin "1") (pinfunction "1_1") (pintype "passive"))
      (node (ref "C3") (pin "1") (pinfunction "1_1") (pintype "passive"))
      (node (ref "P11") (pin "2") (pinfunction "2_2") (pintype "passive"))
      (node (ref "P11") (pin "4") (pinfunction "4_4") (pintype "passive"))
      (node (ref "P11") (pin "6") (pinfunction "6_6") (pintype "passive"))
      (node (ref "P3") (pin "12") (pinfunction "12_12") (pintype "passive"))
      (node (ref "P3") (pin "14") (pinfunction "14_14") (pintype "passive"))
      (node (ref "P3") (pin "16") (pinfunction "16_16") (pintype "passive"))
      (node (ref "R1") (pin "1") (pintype "passive"))
      (node (ref "R2") (pin "1") (pintype "passive"))
      (node (ref "R27") (pin "2") (pinfunction "2_2") (pintype "passive"))
      (node (ref "R4") (pin "1") (pintype "passive"))
    )
    (net (code "105") (name "3V3S") (class "Default")
      (node (ref "C4") (pin "2") (pinfunction "2_2") (pintype "passive"))
      (node (ref "D1") (pin "1") (pinfunction "A_1") (pintype "passive"))
      (node (ref "P2") (pin "4") (pintype "passive"))
      (node (ref "P2") (pin "5") (pintype "passive"))
      (node (ref "R2") (pin "2") (pintype "passive"))
      (node (ref "R8") (pin "1") (pintype "passive"))
      (node (ref "R9") (pin "1") (pintype "passive"))
      (node (ref "U1") (pin "2") (pinfunction "Vout_2") (pintype "passive"))
    )
    (net (code "106") (name "5V") (class "Default")
      (node (ref "C11") (pin "1") (pinfunction "1_1") (pintype "passive"))
      (node (ref "C6") (pin "1") (pinfunction "1_1") (pintype "passive"))
      (node (ref "F1") (pin "1") (pinfunction "1_1") (pintype "passive"))
      (node (ref "P10") (pin "10") (pinfunction "10_10") (pintype "passive"))
      (node (ref "P10") (pin "9") (pinfunction "9_9") (pintype "passive"))
      (node (ref "P14") (pin "A4") (pinfunction "VBUS_A4") (pintype "bidirectional"))
      (node (ref "P14") (pin "B4") (pinfunction "VBUS_B4") (pintype "bidirectional"))
      (node (ref "P15") (pin "A4") (pinfunction "VBUS_A4") (pintype "bidirectional"))
      (node (ref "P15") (pin "B4") (pinfunction "VBUS_B4") (pintype "bidirectional"))
      (node (ref "P3") (pin "10") (pinfunction "10_10") (pintype "passive"))
      (node (ref "P3") (pin "6") (pinfunction "6_6") (pintype "passive"))
      (node (ref "P3") (pin "8") (pinfunction "8_8") (pintype "passive"))
      (node (ref "P4") (pin "1") (pinfunction "+5V_1") (pintype "power_in"))
      (node (ref "P5") (pin "1") (pinfunction "+5V_1") (pintype "power_in"))
    )
    (net (code "107") (name "GND") (class "Default")
      (node (ref "C1") (pin "2") (pinfunction "2_2") (pintype "passive"))
      (node (ref "C10") (pin "1") (pinfunction "1_1") (pintype "passive"))
      (node (ref "C11") (pin "2") (pinfunction "2_2") (pintype "passive"))
      (node (ref "C12") (pin "1") (pinfunction "1_1") (pintype "passive"))
      (node (ref "C13") (pin "2") (pinfunction "2_2") (pintype "passive"))
      (node (ref "C14") (pin "1") (pinfunction "1_1") (pintype "passive"))
      (node (ref "C2") (pin "2") (pinfunction "2_2") (pintype "passive"))
      (node (ref "C3") (pin "2") (pinfunction "2_2") (pintype "passive"))
      (node (ref "C4") (pin "1") (pinfunction "1_1") (pintype "passive"))
      (node (ref "C42") (pin "1") (pinfunction "1_1") (pintype "passive"))
      (node (ref "C45") (pin "2") (pinfunction "2_2") (pintype "passive"))
      (node (ref "C46") (pin "2") (pinfunction "2_2") (pintype "passive"))
      (node (ref "C47") (pin "1") (pinfunction "1_1") (pintype "passive"))
      (node (ref "C5") (pin "2") (pinfunction "2_2") (pintype "passive"))
      (node (ref "C6") (pin "2") (pinfunction "2_2") (pintype "passive"))
      (node (ref "C7") (pin "1") (pinfunction "1_1") (pintype "passive"))
      (node (ref "C8") (pin "1") (pinfunction "1_1") (pintype "passive"))
      (node (ref "C9") (pin "1") (pinfunction "1_1") (pintype "passive"))
      (node (ref "P1") (pin "2") (pinfunction "2_2") (pintype "passive"))
      (node (ref "P10") (pin "5") (pinfunction "5_5") (pintype "passive"))
      (node (ref "P10") (pin "6") (pinfunction "6_6") (pintype "passive"))
      (node (ref "P14") (pin "A1") (pinfunction "GND_A1") (pintype "bidirectional"))
      (node (ref "P14") (pin "B1") (pinfunction "GND_B1") (pintype "bidirectional"))
      (node (ref "P15") (pin "A1") (pinfunction "GND_A1") (pintype "bidirectional"))
      (node (ref "P15") (pin "B1") (pinfunction "GND_B1") (pintype "bidirectional"))
      (node (ref "P2") (pin "8") (pintype "passive"))
      (node (ref "P3") (pin "1") (pinfunction "1_1") (pintype "passive"))
      (node (ref "P3") (pin "11") (pinfunction "11_11") (pintype "passive"))
      (node (ref "P3") (pin "13") (pinfunction "13_13") (pintype "passive"))
      (node (ref "P3") (pin "15") (pinfunction "15_15") (pintype "passive"))
      (node (ref "P3") (pin "2") (pinfunction "2_2") (pintype "passive"))
      (node (ref "P3") (pin "3") (pinfunction "3_3") (pintype "passive"))
      (node (ref "P3") (pin "4") (pinfunction "4_4") (pintype "passive"))
      (node (ref "P3") (pin "5") (pinfunction "5_5") (pintype "passive"))
      (node (ref "P3") (pin "7") (pinfunction "7_7") (pintype "passive"))
      (node (ref "P3") (pin "9") (pinfunction "9_9") (pintype "passive"))
      (node (ref "P4") (pin "4") (pinfunction "GND_4") (pintype "power_in"))
      (node (ref "P4") (pin "5") (pinfunction "GND_5") (pintype "power_in"))
      (node (ref "P4") (pin "6") (pinfunction "GND_6") (pintype "power_in"))
      (node (ref "P5") (pin "4") (pinfunction "GND_4") (pintype "power_in"))
      (node (ref "P5") (pin "5") (pinfunction "GND_5") (pintype "power_in"))
      (node (ref "P5") (pin "6") (pinfunction "GND_6") (pintype "power_in"))
      (node (ref "P6") (pin "25") (pinfunction "25_25") (pintype "passive"))
      (node (ref "P6") (pin "26") (pinfunction "26_26") (pintype "passive"))
      (node (ref "P6") (pin "27") (pinfunction "27_27") (pintype "passive"))
      (node (ref "P6") (pin "28") (pinfunction "28_28") (pintype "passive"))
      (node (ref "P6") (pin "5") (pinfunction "5_5") (pintype "passive"))
      (node (ref "P7") (pin "6") (pinfunction "6_6") (pintype "passive"))
      (node (ref "P9") (pin "1") (pinfunction "1_1") (pintype "passive"))
      (node (ref "P9") (pin "2") (pinfunction "2_2") (pintype "passive"))
      (node (ref "P9") (pin "39") (pinfunction "39_39") (pintype "passive"))
      (node (ref "P9") (pin "40") (pinfunction "40_40") (pintype "passive"))
      (node (ref "P9") (pin "41") (pinfunction "41_41") (pintype "passive"))
      (node (ref "P9") (pin "42") (pinfunction "42_42") (pintype "passive"))
      (node (ref "R17") (pin "1") (pinfunction "1_1") (pintype "passive"))
      (node (ref "R21") (pin "2") (pinfunction "2_2") (pintype "passive"))
      (node (ref "R22") (pin "2") (pinfunction "2_2") (pintype "passive"))
      (node (ref "R23") (pin "2") (pinfunction "2_2") (pintype "passive"))
      (node (ref "R24") (pin "2") (pinfunction "2_2") (pintype "passive"))
      (node (ref "R25") (pin "2") (pinfunction "2_2") (pintype "passive"))
      (node (ref "R26") (pin "2") (pinfunction "2_2") (pintype "passive"))
      (node (ref "R3") (pin "2") (pintype "passive"))
      (node (ref "R5") (pin "1") (pintype "passive"))
      (node (ref "S3") (pin "1") (pinfunction "1_1") (pintype "passive"))
      (node (ref "U1") (pin "1") (pinfunction "GND_1") (pintype "passive"))
      (node (ref "U2") (pin "10") (pinfunction "VSS_5_10") (pintype "power_in"))
      (node (ref "U2") (pin "19") (pinfunction "VSSA_19") (pintype "power_in"))
      (node (ref "U2") (pin "27") (pinfunction "VSS_4_27") (pintype "power_in"))
      (node (ref "U2") (pin "49") (pinfunction "VSS_1_49") (pintype "power_in"))
      (node (ref "U2") (pin "74") (pinfunction "VSS_2_74") (pintype "power_in"))
      (node (ref "U2") (pin "99") (pinfunction "VSS_3_99") (pintype "power_in"))
    )
    (net (code "108") (name "Net-(D1-K)") (class "Default")
      (node (ref "D1") (pin "2") (pinfunction "K_2") (pintype "passive"))
      (node (ref "R3") (pin "1") (pintype "passive"))
    )
    (net (code "109") (name "Net-(D3-A)") (class "Default")
      (node (ref "D3") (pin "1") (pinfunction "A_1") (pintype "passive"))
      (node (ref "R1") (pin "2") (pintype "passive"))
    )
    (net (code "110") (name "Net-(D4-A)") (class "Default")
      (node (ref "D4") (pin "1") (pinfunction "A_1") (pintype "passive"))
      (node (ref "R4") (pin "2") (pintype "passive"))
    )
    (net (code "111") (name "Net-(P2-Pad9)") (class "Default")
      (node (ref "P2") (pin "9") (pintype "passive"))
      (node (ref "R8") (pin "2") (pintype "passive"))
    )
    (net (code "112") (name "Net-(P2-Pad12)") (class "Default")
      (node (ref "P2") (pin "12") (pintype "passive"))
      (node (ref "R9") (pin "2") (pintype "passive"))
    )
    (net (code "113") (name "Net-(P14-CC-PadA5)") (class "Default")
      (node (ref "P14") (pin "A5") (pinfunction "CC_A5") (pintype "bidirectional"))
      (node (ref "R25") (pin "1") (pinfunction "1_1") (pintype "passive"))
    )
    (net (code "114") (name "Net-(P14-CC-PadB5)") (class "Default")
      (node (ref "P14") (pin "B5") (pinfunction "CC_B5") (pintype "bidirectional"))
      (node (ref "R26") (pin "1") (pinfunction "1_1") (pintype "passive"))
    )
    (net (code "115") (name "Net-(P15-CC-PadA5)") (class "Default")
      (node (ref "P15") (pin "A5") (pinfunction "CC_A5") (pintype "bidirectional"))
      (node (ref "R23") (pin "1") (pinfunction "1_1") (pintype "passive"))
    )
    (net (code "116") (name "Net-(P15-CC-PadB5)") (class "Default")
      (node (ref "P15") (pin "B5") (pinfunction "CC_B5") (pintype "bidirectional"))
      (node (ref "R24") (pin "1") (pinfunction "1_1") (pintype "passive"))
    )
    (net (code "117") (name "Net-(R5-Pad2)") (class "Default")
      (node (ref "R5") (pin "2") (pintype "passive"))
      (node (ref "S2") (pin "2") (pinfunction "2_2") (pintype "passive"))
    )
    (net (code "118") (name "Net-(R20-Pad2)") (class "Default")
      (node (ref "R20") (pin "2") (pinfunction "2_2") (pintype "passive"))
      (node (ref "S4") (pin "2") (pinfunction "2_2") (pintype "passive"))
    )
    (net (code "119") (name "Net-(S1-COMMON)") (class "Default")
      (node (ref "F1") (pin "2") (pinfunction "2_2") (pintype "passive"))
      (node (ref "S1") (pin "1") (pinfunction "COMMON_1") (pintype "passive"))
    )
    (net (code "120") (name "Net-(S1-NC)") (class "Default")
      (node (ref "C1") (pin "1") (pinfunction "1_1") (pintype "passive"))
      (node (ref "S1") (pin "2") (pinfunction "NC_2") (pintype "passive"))
      (node (ref "U1") (pin "3") (pinfunction "Vin_3") (pintype "passive"))
    )
    (net (code "121") (name "unconnected-(P2-Pad7)") (class "Default")
      (node (ref "P2") (pin "7") (pintype "passive"))
    )
    (net (code "122") (name "unconnected-(P14-RFU1-PadA8)") (class "Default")
      (node (ref "P14") (pin "A8") (pinfunction "RFU1_A8") (pintype "bidirectional+no_connect"))
    )
    (net (code "123") (name "unconnected-(P14-RFU1-PadB8)") (class "Default")
      (node (ref "P14") (pin "B8") (pinfunction "RFU1_B8") (pintype "bidirectional+no_connect"))
    )
    (net (code "124") (name "unconnected-(P15-RFU1-PadA8)") (class "Default")
      (node (ref "P15") (pin "A8") (pinfunction "RFU1_A8") (pintype "bidirectional+no_connect"))
    )
    (net (code "125") (name "unconnected-(P15-RFU1-PadB8)") (class "Default")
      (node (ref "P15") (pin "B8") (pinfunction "RFU1_B8") (pintype "bidirectional+no_connect"))
    )
    (net (code "126") (name "unconnected-(S1-NO-Pad3)") (class "Default")
      (node (ref "S1") (pin "3") (pinfunction "NO_3") (pintype "passive"))
    )
  )
)
